# optoparaE3.net
KiCad netlist of a schematic drawn in Altium Designer
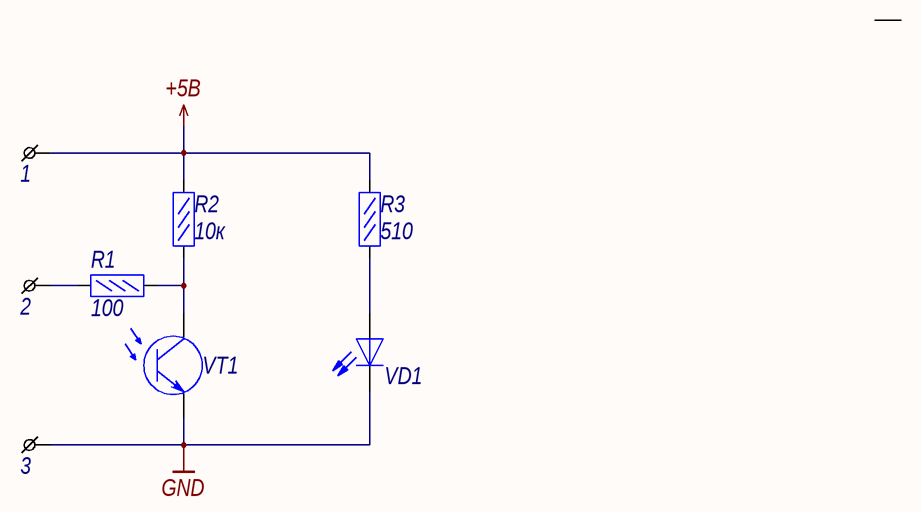
[diagram p0: optoparaE3.SchDoc]

(export (version "E")
  (design (tool "Eeschema 10.0.6"))
  (components
    (comp (ref "1") (value "MNT_HOLE") (footprint "TP_1X1") (libsource (lib "mount_parts") (part "MNT_HOLE")))
    (comp (ref "2") (value "MNT_HOLE") (footprint "TP_1X1") (libsource (lib "mount_parts") (part "MNT_HOLE")))
    (comp (ref "3") (value "MNT_HOLE") (footprint "TP_1X1") (libsource (lib "mount_parts") (part "MNT_HOLE")))
    (comp (ref "R1")
      (value "100")
      (footprint "R0603")
      (description "Резистор 100 Ом 0,1Вт 1%")
      (fields (field (name "MANUFACTURER") "YAGEO") (field (name "TOLERANCE") "1%"))
      (libsource (lib "resistors") (part "RC0603FR-07100RL"))
    )
    (comp (ref "R2")
      (value "10к")
      (footprint "R0603")
      (description "Резистор 10кОм 0,063Вт 1%")
      (fields (field (name "MANUFACTURER") "YAGEO") (field (name "TOLERANCE") "1%"))
      (libsource (lib "resistors") (part "RC0603FR-0710KL"))
    )
    (comp (ref "R3")
      (value "510")
      (footprint "R0603")
      (description "Резистор 510 Ом 0,1Вт 1%")
      (fields (field (name "MANUFACTURER") "YAGEO") (field (name "TOLERANCE") "1%"))
      (libsource (lib "resistors") (part "RC0603FR-07510RL"))
    )
    (comp (ref "VD1")
      (value "~")
      (footprint "LED_5mm")
      (description "ИК светодиод")
      (libsource (lib "diodes") (part "IR_LED"))
    )
    (comp (ref "VT1")
      (value "-")
      (footprint "LED_5mm")
      (description "Биполярный NPN транзистор")
      (libsource (lib "transistors") (part "BJTfoto"))
    )
  )
  (nets
    (net (code "1") (name "+5В") (class "Default")
      (node (ref "1") (pin "1") (pinfunction "1_1") (pintype "passive"))
      (node (ref "R2") (pin "2") (pinfunction "2_2") (pintype "passive"))
      (node (ref "R3") (pin "2") (pinfunction "2_2") (pintype "passive"))
    )
    (net (code "2") (name "GND") (class "Default")
      (node (ref "3") (pin "1") (pinfunction "1_1") (pintype "passive"))
      (node (ref "VD1") (pin "2") (pinfunction "K_2") (pintype "passive"))
      (node (ref "VT1") (pin "2") (pintype "passive"))
    )
    (net (code "3") (name "Net-(2-Pad1)") (class "Default")
      (node (ref "2") (pin "1") (pinfunction "1_1") (pintype "passive"))
      (node (ref "R1") (pin "1") (pinfunction "1_1") (pintype "passive"))
    )
    (net (code "4") (name "Net-(R1-Pad2)") (class "Default")
      (node (ref "R1") (pin "2") (pinfunction "2_2") (pintype "passive"))
      (node (ref "R2") (pin "1") (pinfunction "1_1") (pintype "passive"))
      (node (ref "VT1") (pin "1") (pintype "passive"))
    )
    (net (code "5") (name "Net-(VD1-A)") (class "Default")
      (node (ref "R3") (pin "1") (pinfunction "1_1") (pintype "passive"))
      (node (ref "VD1") (pin "1") (pinfunction "A_1") (pintype "passive"))
    )
  )
)
